# UI_BUTTON_LED.net
KiCad netlist of a schematic drawn in Altium Designer
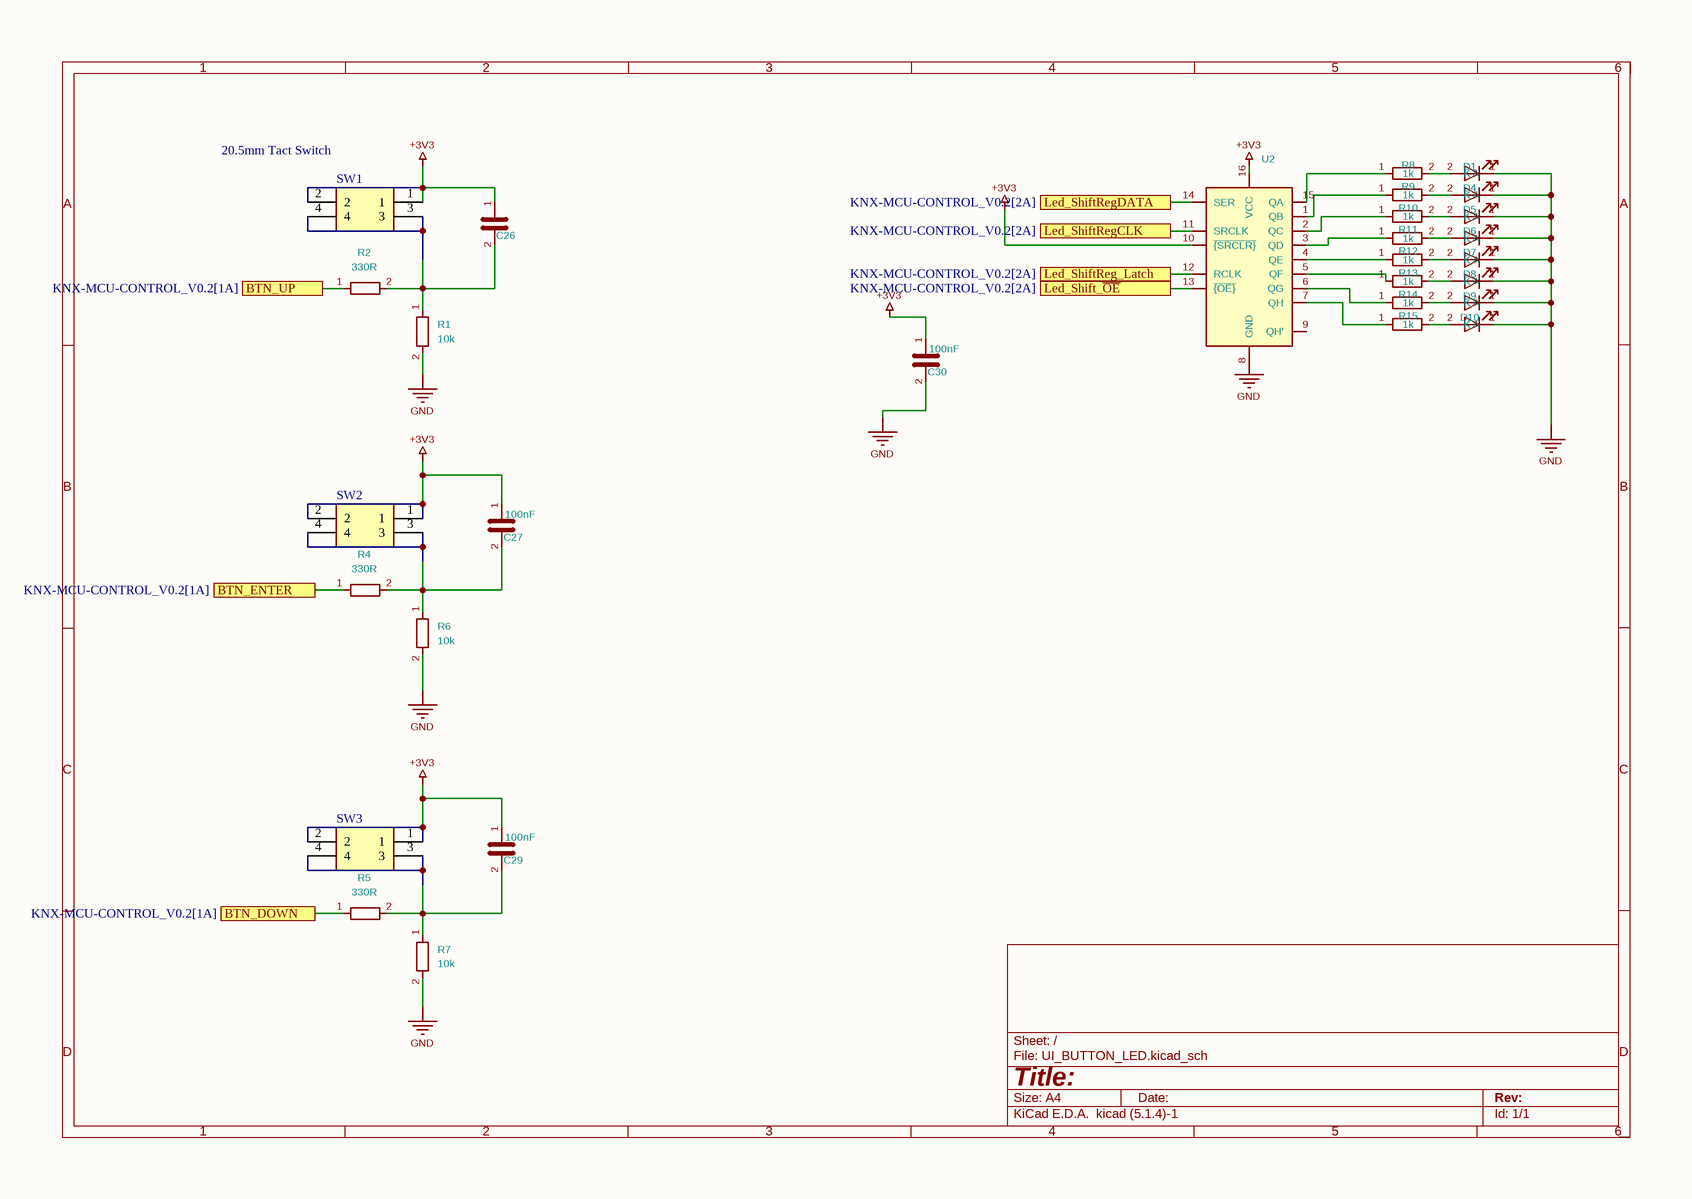
[diagram p0: UI_BUTTON_LED.SchDoc]

(export (version "E")
  (design (tool "Eeschema 10.0.6"))
  (components
    (comp (ref "C26")
      (value "100nF")
      (footprint "C_0603_1608Metric")
      (fields
        (field (name "MANUFACTURER PART NUMBER") "CC0603KRX7R9BB104")
        (field (name "MANUFACTURER") "YAGEO")
      )
      (libsource (lib "*") (part "C_3"))
    )
    (comp (ref "C27")
      (value "100nF")
      (footprint "C_0603_1608Metric")
      (fields
        (field (name "MANUFACTURER PART NUMBER") "CC0603KRX7R9BB104")
        (field (name "MANUFACTURER") "YAGEO")
      )
      (libsource (lib "*") (part "C_3"))
    )
    (comp (ref "C29")
      (value "100nF")
      (footprint "C_0603_1608Metric")
      (fields
        (field (name "MANUFACTURER PART NUMBER") "CC0603KRX7R9BB104")
        (field (name "MANUFACTURER") "YAGEO")
      )
      (libsource (lib "*") (part "C_3"))
    )
    (comp (ref "C30")
      (value "100nF")
      (footprint "C_0603_1608Metric")
      (fields
        (field (name "MANUFACTURER PART NUMBER") "CC0603KRX7R9BB104")
        (field (name "MANUFACTURER") "YAGEO")
      )
      (libsource (lib "*") (part "C_1"))
    )
    (comp (ref "D1")
      (value "LED")
      (footprint "LED_0603_1608Metric")
      (fields
        (field (name "MANUFACTURER") "LITEON")
        (field (name "MANUFACTURER PART NUMBER") "LTST-C190KFKT-5A")
      )
      (libsource (lib "Device") (part "LED"))
    )
    (comp (ref "D4")
      (value "LED")
      (footprint "LED_0603_1608Metric")
      (fields
        (field (name "MANUFACTURER") "LITEON")
        (field (name "MANUFACTURER PART NUMBER") "LTST-C190KFKT-5A")
      )
      (libsource (lib "Device") (part "LED"))
    )
    (comp (ref "D5")
      (value "LED")
      (footprint "LED_0603_1608Metric")
      (fields
        (field (name "MANUFACTURER") "LITEON")
        (field (name "MANUFACTURER PART NUMBER") "LTST-C190KFKT-5A")
      )
      (libsource (lib "Device") (part "LED"))
    )
    (comp (ref "D6")
      (value "LED")
      (footprint "LED_0603_1608Metric")
      (fields
        (field (name "MANUFACTURER") "LITEON")
        (field (name "MANUFACTURER PART NUMBER") "LTST-C190KFKT-5A")
      )
      (libsource (lib "Device") (part "LED"))
    )
    (comp (ref "D7")
      (value "LED")
      (footprint "LED_0603_1608Metric")
      (fields
        (field (name "MANUFACTURER") "LITEON")
        (field (name "MANUFACTURER PART NUMBER") "LTST-C190KFKT-5A")
      )
      (libsource (lib "Device") (part "LED"))
    )
    (comp (ref "D8")
      (value "LED")
      (footprint "LED_0603_1608Metric")
      (fields
        (field (name "MANUFACTURER") "LITEON")
        (field (name "MANUFACTURER PART NUMBER") "LTST-C190KFKT-5A")
      )
      (libsource (lib "Device") (part "LED"))
    )
    (comp (ref "D9")
      (value "LED")
      (footprint "LED_0603_1608Metric")
      (fields
        (field (name "MANUFACTURER") "LITEON")
        (field (name "MANUFACTURER PART NUMBER") "LTST-C190KFKT-5A")
      )
      (libsource (lib "Device") (part "LED"))
    )
    (comp (ref "D10")
      (value "LED")
      (footprint "LED_0603_1608Metric")
      (fields
        (field (name "MANUFACTURER") "LITEON")
        (field (name "MANUFACTURER PART NUMBER") "LTST-C190KFKT-5A")
      )
      (libsource (lib "Device") (part "LED"))
    )
    (comp (ref "R1")
      (value "10k")
      (footprint "R_0603_1608Metric")
      (fields (field (name "MANUFACTURER") "FOJAN") (field (name "MANUFACTURER PART NUMBER") "FRC0603J103TS"))
      (libsource (lib "") (part "R_1"))
    )
    (comp (ref "R2")
      (value "330R")
      (footprint "R_0603_1608Metric")
      (fields
        (field (name "MANUFACTURER") "FOJAN")
        (field (name "MANUFACTURER PART NUMBER") "FRC0603J331 TS")
      )
      (libsource (lib "Device") (part "R"))
    )
    (comp (ref "R4")
      (value "330R")
      (footprint "R_0603_1608Metric")
      (fields
        (field (name "MANUFACTURER") "FOJAN")
        (field (name "MANUFACTURER PART NUMBER") "FRC0603J331 TS")
      )
      (libsource (lib "Device") (part "R"))
    )
    (comp (ref "R5")
      (value "330R")
      (footprint "R_0603_1608Metric")
      (fields
        (field (name "MANUFACTURER") "FOJAN")
        (field (name "MANUFACTURER PART NUMBER") "FRC0603J331 TS")
      )
      (libsource (lib "Device") (part "R"))
    )
    (comp (ref "R6")
      (value "10k")
      (footprint "R_0603_1608Metric")
      (fields (field (name "MANUFACTURER") "FOJAN") (field (name "MANUFACTURER PART NUMBER") "FRC0603J103TS"))
      (libsource (lib "") (part "R_1"))
    )
    (comp (ref "R7")
      (value "10k")
      (footprint "R_0603_1608Metric")
      (fields (field (name "MANUFACTURER") "FOJAN") (field (name "MANUFACTURER PART NUMBER") "FRC0603J103TS"))
      (libsource (lib "") (part "R_1"))
    )
    (comp (ref "R8")
      (value "1k")
      (footprint "R_0603_1608Metric")
      (fields
        (field (name "MANUFACTURER") "YAGEO")
        (field (name "MANUFACTURER PART NUMBER") "RC0603JR-071KL")
      )
      (libsource (lib "Device") (part "R"))
    )
    (comp (ref "R9")
      (value "1k")
      (footprint "R_0603_1608Metric")
      (fields
        (field (name "MANUFACTURER") "YAGEO")
        (field (name "MANUFACTURER PART NUMBER") "RC0603JR-071KL")
      )
      (libsource (lib "Device") (part "R"))
    )
    (comp (ref "R10")
      (value "1k")
      (footprint "R_0603_1608Metric")
      (fields
        (field (name "MANUFACTURER") "YAGEO")
        (field (name "MANUFACTURER PART NUMBER") "RC0603JR-071KL")
      )
      (libsource (lib "Device") (part "R"))
    )
    (comp (ref "R11")
      (value "1k")
      (footprint "R_0603_1608Metric")
      (fields
        (field (name "MANUFACTURER") "YAGEO")
        (field (name "MANUFACTURER PART NUMBER") "RC0603JR-071KL")
      )
      (libsource (lib "Device") (part "R"))
    )
    (comp (ref "R12")
      (value "1k")
      (footprint "R_0603_1608Metric")
      (fields
        (field (name "MANUFACTURER") "YAGEO")
        (field (name "MANUFACTURER PART NUMBER") "RC0603JR-071KL")
      )
      (libsource (lib "Device") (part "R"))
    )
    (comp (ref "R13")
      (value "1k")
      (footprint "R_0603_1608Metric")
      (fields
        (field (name "MANUFACTURER") "YAGEO")
        (field (name "MANUFACTURER PART NUMBER") "RC0603JR-071KL")
      )
      (libsource (lib "Device") (part "R"))
    )
    (comp (ref "R14")
      (value "1k")
      (footprint "R_0603_1608Metric")
      (fields
        (field (name "MANUFACTURER") "YAGEO")
        (field (name "MANUFACTURER PART NUMBER") "RC0603JR-071KL")
      )
      (libsource (lib "Device") (part "R"))
    )
    (comp (ref "R15")
      (value "1k")
      (footprint "R_0603_1608Metric")
      (fields
        (field (name "MANUFACTURER") "YAGEO")
        (field (name "MANUFACTURER PART NUMBER") "RC0603JR-071KL")
      )
      (libsource (lib "Device") (part "R"))
    )
    (comp (ref "SW1")
      (value "TSA06141-225B532CA-3C00")
      (footprint "SamacSys:TL1105")
      (description "Through Hole-4P,8.2x7.6mm")
      (fields (field (name "MANUFACTURER") "Khon"))
      (libsource (lib "*") (part "TL1105BF160Q"))
    )
    (comp (ref "SW2")
      (value "TSA06141-225B532CA-3C00")
      (footprint "SamacSys:TL1105")
      (description "Through Hole-4P,8.2x7.6mm")
      (fields (field (name "MANUFACTURER") "Khon"))
      (libsource (lib "*") (part "TL1105BF160Q"))
    )
    (comp (ref "SW3")
      (value "TSA06141-225B532CA-3C00")
      (footprint "SamacSys:TL1105")
      (description "Through Hole-4P,8.2x7.6mm")
      (fields (field (name "MANUFACTURER") "Khon"))
      (libsource (lib "*") (part "TL1105BF160Q"))
    )
    (comp (ref "U2")
      (value "74HC595PW,118")
      (footprint "TSSOP-16_4.4x5mm_P0.65mm")
      (fields (field (name "MANUFACTURER") "Nexperia"))
      (libsource (lib "74xx") (part "74HC595"))
    )
  )
  (nets
    (net (code "1") (name "+3V3") (class "Default")
      (node (ref "C26") (pin "1") (pinfunction "1_1") (pintype "passive"))
      (node (ref "C27") (pin "1") (pinfunction "1_1") (pintype "passive"))
      (node (ref "C29") (pin "1") (pinfunction "1_1") (pintype "passive"))
      (node (ref "C30") (pin "1") (pinfunction "1_1") (pintype "passive"))
      (node (ref "SW1") (pin "1") (pinfunction "1_1") (pintype "passive"))
      (node (ref "SW1") (pin "2") (pinfunction "2_2") (pintype "passive"))
      (node (ref "SW2") (pin "1") (pinfunction "1_1") (pintype "passive"))
      (node (ref "SW2") (pin "2") (pinfunction "2_2") (pintype "passive"))
      (node (ref "SW3") (pin "1") (pinfunction "1_1") (pintype "passive"))
      (node (ref "SW3") (pin "2") (pinfunction "2_2") (pintype "passive"))
      (node (ref "U2") (pin "10") (pinfunction "~{{SRCLR}}_10") (pintype "passive"))
      (node (ref "U2") (pin "16") (pinfunction "VCC_16") (pintype "passive"))
    )
    (net (code "2") (name "/BTN_DOWN") (class "Default")
      (node (ref "R5") (pin "1") (pinfunction "1_1") (pintype "passive"))
    )
    (net (code "3") (name "/BTN_ENTER") (class "Default")
      (node (ref "R4") (pin "1") (pinfunction "1_1") (pintype "passive"))
    )
    (net (code "4") (name "/BTN_UP") (class "Default")
      (node (ref "R2") (pin "1") (pinfunction "1_1") (pintype "passive"))
    )
    (net (code "5") (name "/Led_ShiftRegCLK") (class "Default")
      (node (ref "U2") (pin "11") (pinfunction "SRCLK_11") (pintype "passive"))
    )
    (net (code "6") (name "/Led_ShiftRegDATA") (class "Default")
      (node (ref "U2") (pin "14") (pinfunction "SER_14") (pintype "passive"))
    )
    (net (code "7") (name "/Led_ShiftReg_Latch") (class "Default")
      (node (ref "U2") (pin "12") (pinfunction "RCLK_12") (pintype "passive"))
    )
    (net (code "8") (name "/Led_Shift_~{OE}") (class "Default")
      (node (ref "U2") (pin "13") (pinfunction "~{{OE}}_13") (pintype "passive"))
    )
    (net (code "9") (name "GND") (class "Default")
      (node (ref "C30") (pin "2") (pinfunction "2_2") (pintype "passive"))
      (node (ref "D1") (pin "1") (pinfunction "K_1") (pintype "passive"))
      (node (ref "D10") (pin "1") (pinfunction "K_1") (pintype "passive"))
      (node (ref "D4") (pin "1") (pinfunction "K_1") (pintype "passive"))
      (node (ref "D5") (pin "1") (pinfunction "K_1") (pintype "passive"))
      (node (ref "D6") (pin "1") (pinfunction "K_1") (pintype "passive"))
      (node (ref "D7") (pin "1") (pinfunction "K_1") (pintype "passive"))
      (node (ref "D8") (pin "1") (pinfunction "K_1") (pintype "passive"))
      (node (ref "D9") (pin "1") (pinfunction "K_1") (pintype "passive"))
      (node (ref "R1") (pin "2") (pinfunction "2_2") (pintype "passive"))
      (node (ref "R6") (pin "2") (pinfunction "2_2") (pintype "passive"))
      (node (ref "R7") (pin "2") (pinfunction "2_2") (pintype "passive"))
      (node (ref "U2") (pin "8") (pinfunction "GND_8") (pintype "passive"))
    )
    (net (code "10") (name "Net-(C26-Pad2)") (class "Default")
      (node (ref "C26") (pin "2") (pinfunction "2_2") (pintype "passive"))
      (node (ref "R1") (pin "1") (pinfunction "1_1") (pintype "passive"))
      (node (ref "R2") (pin "2") (pinfunction "2_2") (pintype "passive"))
      (node (ref "SW1") (pin "3") (pinfunction "3_3") (pintype "passive"))
      (node (ref "SW1") (pin "4") (pinfunction "4_4") (pintype "passive"))
    )
    (net (code "11") (name "Net-(C27-Pad2)") (class "Default")
      (node (ref "C27") (pin "2") (pinfunction "2_2") (pintype "passive"))
      (node (ref "R4") (pin "2") (pinfunction "2_2") (pintype "passive"))
      (node (ref "R6") (pin "1") (pinfunction "1_1") (pintype "passive"))
      (node (ref "SW2") (pin "3") (pinfunction "3_3") (pintype "passive"))
      (node (ref "SW2") (pin "4") (pinfunction "4_4") (pintype "passive"))
    )
    (net (code "12") (name "Net-(C29-Pad2)") (class "Default")
      (node (ref "C29") (pin "2") (pinfunction "2_2") (pintype "passive"))
      (node (ref "R5") (pin "2") (pinfunction "2_2") (pintype "passive"))
      (node (ref "R7") (pin "1") (pinfunction "1_1") (pintype "passive"))
      (node (ref "SW3") (pin "3") (pinfunction "3_3") (pintype "passive"))
      (node (ref "SW3") (pin "4") (pinfunction "4_4") (pintype "passive"))
    )
    (net (code "13") (name "Net-(D1-A)") (class "Default")
      (node (ref "D1") (pin "2") (pinfunction "A_2") (pintype "passive"))
      (node (ref "R8") (pin "2") (pinfunction "2_2") (pintype "passive"))
    )
    (net (code "14") (name "Net-(D4-A)") (class "Default")
      (node (ref "D4") (pin "2") (pinfunction "A_2") (pintype "passive"))
      (node (ref "R9") (pin "2") (pinfunction "2_2") (pintype "passive"))
    )
    (net (code "15") (name "Net-(D5-A)") (class "Default")
      (node (ref "D5") (pin "2") (pinfunction "A_2") (pintype "passive"))
      (node (ref "R10") (pin "2") (pinfunction "2_2") (pintype "passive"))
    )
    (net (code "16") (name "Net-(D6-A)") (class "Default")
      (node (ref "D6") (pin "2") (pinfunction "A_2") (pintype "passive"))
      (node (ref "R11") (pin "2") (pinfunction "2_2") (pintype "passive"))
    )
    (net (code "17") (name "Net-(D7-A)") (class "Default")
      (node (ref "D7") (pin "2") (pinfunction "A_2") (pintype "passive"))
      (node (ref "R12") (pin "2") (pinfunction "2_2") (pintype "passive"))
    )
    (net (code "18") (name "Net-(D8-A)") (class "Default")
      (node (ref "D8") (pin "2") (pinfunction "A_2") (pintype "passive"))
      (node (ref "R13") (pin "2") (pinfunction "2_2") (pintype "passive"))
    )
    (net (code "19") (name "Net-(D9-A)") (class "Default")
      (node (ref "D9") (pin "2") (pinfunction "A_2") (pintype "passive"))
      (node (ref "R14") (pin "2") (pinfunction "2_2") (pintype "passive"))
    )
    (net (code "20") (name "Net-(D10-A)") (class "Default")
      (node (ref "D10") (pin "2") (pinfunction "A_2") (pintype "passive"))
      (node (ref "R15") (pin "2") (pinfunction "2_2") (pintype "passive"))
    )
    (net (code "21") (name "Net-(U2-QA)") (class "Default")
      (node (ref "R8") (pin "1") (pinfunction "1_1") (pintype "passive"))
      (node (ref "U2") (pin "15") (pinfunction "QA_15") (pintype "passive"))
    )
    (net (code "22") (name "Net-(U2-QB)") (class "Default")
      (node (ref "R9") (pin "1") (pinfunction "1_1") (pintype "passive"))
      (node (ref "U2") (pin "1") (pinfunction "QB_1") (pintype "passive"))
    )
    (net (code "23") (name "Net-(U2-QC)") (class "Default")
      (node (ref "R10") (pin "1") (pinfunction "1_1") (pintype "passive"))
      (node (ref "U2") (pin "2") (pinfunction "QC_2") (pintype "passive"))
    )
    (net (code "24") (name "Net-(U2-QD)") (class "Default")
      (node (ref "R11") (pin "1") (pinfunction "1_1") (pintype "passive"))
      (node (ref "U2") (pin "3") (pinfunction "QD_3") (pintype "passive"))
    )
    (net (code "25") (name "Net-(U2-QE)") (class "Default")
      (node (ref "R12") (pin "1") (pinfunction "1_1") (pintype "passive"))
      (node (ref "U2") (pin "4") (pinfunction "QE_4") (pintype "passive"))
    )
    (net (code "26") (name "Net-(U2-QF)") (class "Default")
      (node (ref "R13") (pin "1") (pinfunction "1_1") (pintype "passive"))
      (node (ref "U2") (pin "5") (pinfunction "QF_5") (pintype "passive"))
    )
    (net (code "27") (name "Net-(U2-QG)") (class "Default")
      (node (ref "R14") (pin "1") (pinfunction "1_1") (pintype "passive"))
      (node (ref "U2") (pin "6") (pinfunction "QG_6") (pintype "passive"))
    )
    (net (code "28") (name "Net-(U2-QH)") (class "Default")
      (node (ref "R15") (pin "1") (pinfunction "1_1") (pintype "passive"))
      (node (ref "U2") (pin "7") (pinfunction "QH_7") (pintype "passive"))
    )
    (net (code "29") (name "unconnected-(U2-QH'-Pad9)") (class "Default")
      (node (ref "U2") (pin "9") (pinfunction "QH'_9") (pintype "passive"))
    )
  )
)
